# PDN.net
KiCad netlist of a schematic drawn in Altium Designer
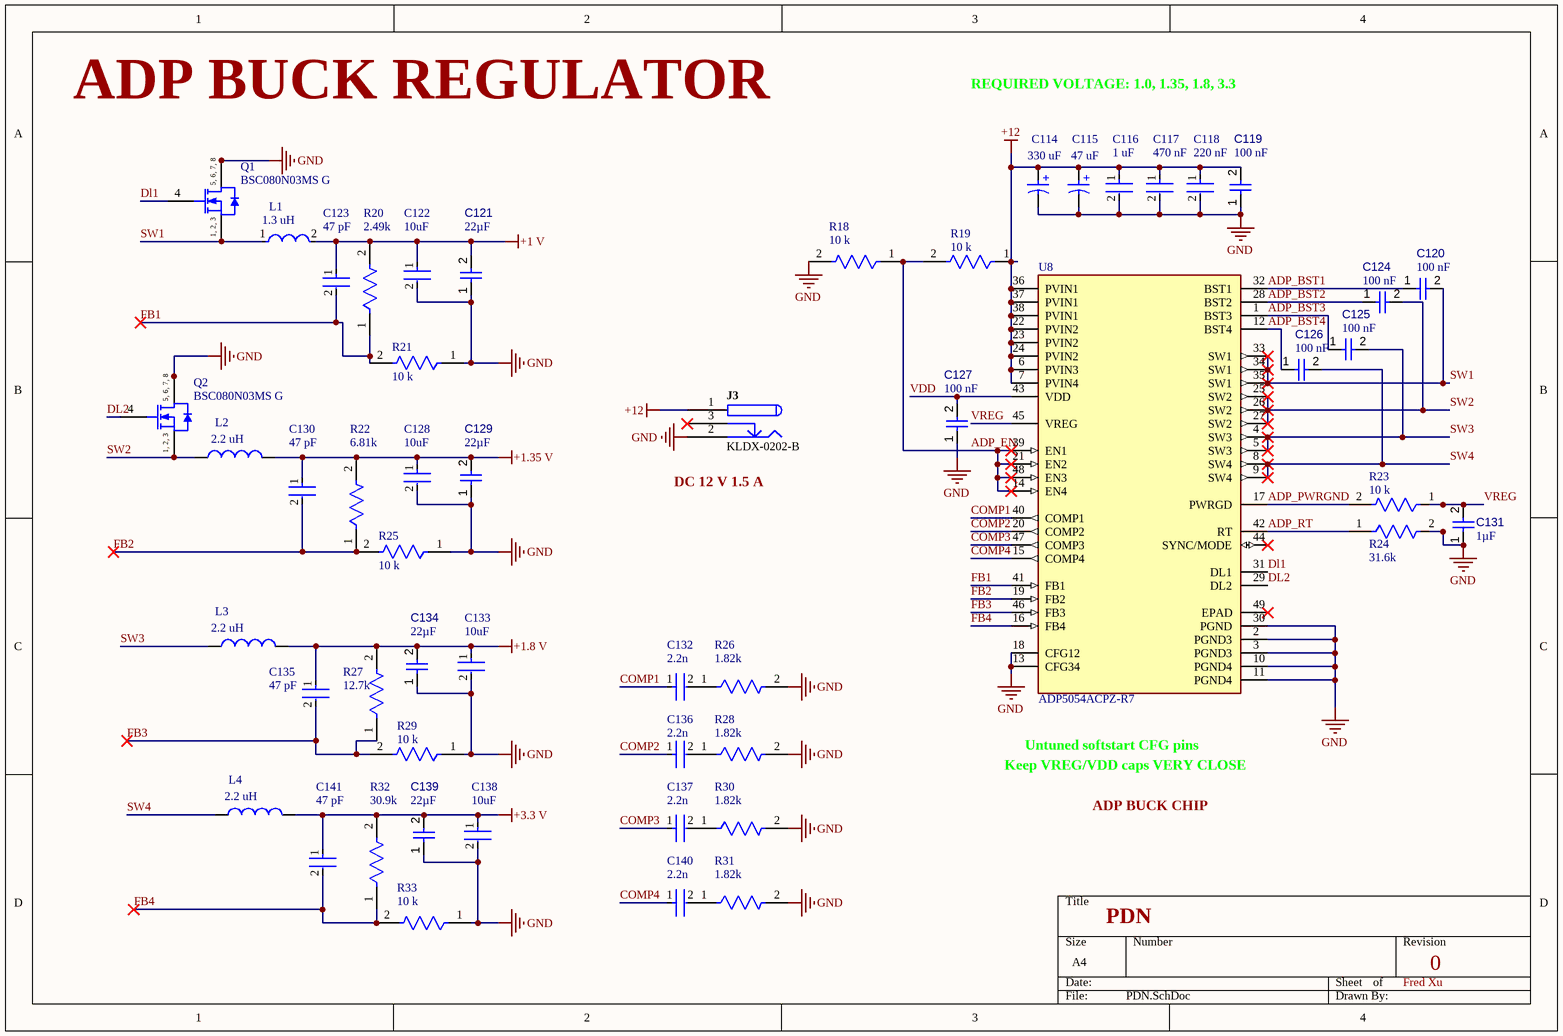
[diagram p0: PDN.SchDoc]

(export (version "E")
  (design (tool "Eeschema 10.0.6"))
  (components
    (comp (ref "C114")
      (value "330 uF")
      (footprint "WCAP-ATLI_D8H11.5")
      (fields (field (name "TOLERANCE") "20%"))
      (libsource (lib "Altium Content Vault") (part "Capacitor_Polarized"))
    )
    (comp (ref "C115")
      (value "47 uF")
      (footprint "WCAP-AT1H_D16H25")
      (description "Cap, 47Uf, 400V, Alu Elec, Radial Rohs Compliant: Yes")
      (libsource (lib "Altium Content Vault") (part "Capacitor_Polarized"))
    )
    (comp (ref "C116")
      (value "1 uF")
      (footprint "FP-GCM155-0_2-MFG")
      (description "Ceramic Capacitor for Automotive 1uF ±20% 10VDC X7S 0402 Paper T/R")
      (libsource (lib "Altium Content Vault") (part "11868f565c42a9108669ba33697ecf6"))
    )
    (comp (ref "C117")
      (value "470 nF")
      (footprint "FP-GRM155-0_05-IPC_B")
      (description "Chip Multilayer Ceramic Capacitors for General Purpose, 0402, 0.47uF, X7R, 15%, 20%, 10V")
      (fields (field (name "TOLERANCE") "20%"))
      (libsource (lib "Altium Content Vault") (part "02cd4be3c70576c341d710602a673aa"))
    )
    (comp (ref "C118")
      (value "220 nF")
      (footprint "FP-CGA2B-IPC_B")
      (description "Cap Ceramic 220nF 25V X7R 20% Pad SMD 0402 +125°C Automotive T/R")
      (fields (field (name "TOLERANCE") "20%"))
      (libsource (lib "Altium Content Vault") (part "b4654b650e69147ec39a6b967a45e02"))
    )
    (comp (ref "C119")
      (value "100 nF")
      (footprint "CAPC1005X56X25LL10T15")
      (description "Chip Capacitor, 0.1 uF, +/- 5%, 16 V, 0402 (1005 Metric)")
      (fields (field (name "TOLERANCE") "5%") (field (name "Comment") "0.1 uF"))
      (libsource (lib "Fred Xu") (part "CAP-NP-2"))
    )
    (comp (ref "C120")
      (value "100 nF")
      (footprint "CAPC1005X56X25LL10T15")
      (description "Chip Capacitor, 0.1 uF, +/- 5%, 16 V, 0402 (1005 Metric), 0.1-1 ohm ESR, 15 MHz-1nH ESL")
      (fields (field (name "TOLERANCE") "5%") (field (name "Comment") "0.1 uF"))
      (libsource (lib "Fred Xu") (part "CAP-NP-2"))
    )
    (comp (ref "C121")
      (value "22µF")
      (footprint "CAPC0805(2012)145_L")
      (description "Chip Capacitor, 22µF +/-40%, 16V, 0805, Thickness 1.45 mm, 5-50 mOhm,  0.5-2 nH")
      (fields (field (name "TOLERANCE") "5%") (field (name "Comment") "Capacitor 22µF +/-40% 16V 0805"))
      (libsource (lib "Fred Xu") (part "CAP-NP-2"))
    )
    (comp (ref "C122")
      (value "10uF")
      (footprint "FP-CL21-IPC_A")
      (fields (field (name "TOLERANCE") "10%"))
      (libsource (lib "Altium Content Vault") (part "b4654b650e69147ec39a6b967a45e02"))
    )
    (comp (ref "C123")
      (value "47 pF")
      (footprint "FP-GQM155-0_05-IPC_A")
      (description "Ceramic Capacitor 47pF  ±5% 100VDC C0G 0402 Paper T/R")
      (fields (field (name "TOLERANCE") "5%"))
      (libsource (lib "Altium Content Vault") (part "11868f565c42a9108669ba33697ecf6"))
    )
    (comp (ref "C124")
      (value "100 nF")
      (footprint "CAPC1005X56X25LL10T15")
      (description "Chip Capacitor, 0.1 uF, +/- 5%, 16 V, 0402 (1005 Metric), 0.1-1 ohm ESR, 15 MHz-1nH ESL")
      (fields (field (name "TOLERANCE") "5%") (field (name "Comment") "0.1 uF"))
      (libsource (lib "Fred Xu") (part "CAP-NP-2"))
    )
    (comp (ref "C125")
      (value "100 nF")
      (footprint "CAPC1005X56X25LL10T15")
      (description "Chip Capacitor, 0.1 uF, +/- 5%, 16 V, 0402 (1005 Metric), 0.1-1 ohm ESR, 15 MHz-1nH ESL")
      (fields (field (name "TOLERANCE") "5%") (field (name "Comment") "0.1 uF"))
      (libsource (lib "Fred Xu") (part "CAP-NP-2"))
    )
    (comp (ref "C126")
      (value "100 nF")
      (footprint "CAPC1005X56X25LL10T15")
      (description "Chip Capacitor, 0.1 uF, +/- 5%, 16 V, 0402 (1005 Metric), 0.1-1 ohm ESR, 15 MHz-1nH ESL")
      (fields (field (name "TOLERANCE") "5%") (field (name "Comment") "0.1 uF"))
      (libsource (lib "Fred Xu") (part "CAP-NP-2"))
    )
    (comp (ref "C127")
      (value "100 nF")
      (footprint "CAPC1005X56X25LL10T15")
      (description "Chip Capacitor, 0.1 uF, +/- 5%, 16 V, 0402 (1005 Metric)")
      (fields (field (name "TOLERANCE") "5%") (field (name "Comment") "0.1 uF"))
      (libsource (lib "Fred Xu") (part "CAP-NP-2"))
    )
    (comp (ref "C128")
      (value "10uF")
      (footprint "FP-CL21-IPC_A")
      (fields (field (name "TOLERANCE") "10%"))
      (libsource (lib "Altium Content Vault") (part "b4654b650e69147ec39a6b967a45e02"))
    )
    (comp (ref "C129")
      (value "22µF")
      (footprint "CAPC0805(2012)145_L")
      (description "Chip Capacitor, 22µF +/-40%, 16V, 0805, Thickness 1.45 mm, 5-50 mOhm,  0.5-2 nH")
      (fields (field (name "TOLERANCE") "5%") (field (name "Comment") "Capacitor 22µF +/-40% 16V 0805"))
      (libsource (lib "Fred Xu") (part "CAP-NP-2"))
    )
    (comp (ref "C130")
      (value "47 pF")
      (footprint "FP-GQM155-0_05-IPC_A")
      (description "Ceramic Capacitor 47pF  ±5% 100VDC C0G 0402 Paper T/R")
      (fields (field (name "TOLERANCE") "5%"))
      (libsource (lib "Altium Content Vault") (part "11868f565c42a9108669ba33697ecf6"))
    )
    (comp (ref "C131")
      (value "1µF")
      (footprint "CAPC0603(1608)100_L")
      (description "Chip Capacitor, 1µF +/-40%, 50V, 0603, Thickness 1 mm")
      (fields (field (name "TOLERANCE") "10%") (field (name "Comment") "Capacitor 1µF +/-40% 50V 0603"))
      (libsource (lib "Fred Xu") (part "CAP-NP-2"))
    )
    (comp (ref "C132")
      (value "2.2n")
      (footprint "FP-C0402-BB-MFG")
      (description "C0402 2,200 pF C0G 0.02 25 V")
      (fields
        (field (name "MANUFACTURER PART NUMBER") "C0402C222G3GACTU")
        (field (name "OCTOPART") "https://octopart.com/c0402c222g3gactu-kemet-87368565")
      )
      (libsource (lib "Altium Content Vault") (part "b4654b650e69147ec39a6b967a45e02"))
    )
    (comp (ref "C133")
      (value "10uF")
      (footprint "FP-CL21-IPC_A")
      (fields (field (name "TOLERANCE") "10%"))
      (libsource (lib "Altium Content Vault") (part "b4654b650e69147ec39a6b967a45e02"))
    )
    (comp (ref "C134")
      (value "22µF")
      (footprint "CAPC0805(2012)145_L")
      (description "Chip Capacitor, 22µF +/-40%, 16V, 0805, Thickness 1.45 mm, 5-50 mOhm,  0.5-2 nH")
      (fields (field (name "TOLERANCE") "5%") (field (name "Comment") "Capacitor 22µF +/-40% 16V 0805"))
      (libsource (lib "Fred Xu") (part "CAP-NP-2"))
    )
    (comp (ref "C135")
      (value "47 pF")
      (footprint "FP-GQM155-0_05-IPC_A")
      (description "Ceramic Capacitor 47pF  ±5% 100VDC C0G 0402 Paper T/R")
      (fields (field (name "TOLERANCE") "5%"))
      (libsource (lib "Altium Content Vault") (part "11868f565c42a9108669ba33697ecf6"))
    )
    (comp (ref "C136")
      (value "2.2n")
      (footprint "FP-C0402-BB-MFG")
      (description "C0402 2,200 pF C0G 0.02 25 V")
      (fields
        (field (name "MANUFACTURER PART NUMBER") "C0402C222G3GACTU")
        (field (name "OCTOPART") "https://octopart.com/c0402c222g3gactu-kemet-87368565")
      )
      (libsource (lib "Altium Content Vault") (part "b4654b650e69147ec39a6b967a45e02"))
    )
    (comp (ref "C137")
      (value "2.2n")
      (footprint "FP-C0402-BB-MFG")
      (description "C0402 2,200 pF C0G 0.02 25 V")
      (fields
        (field (name "MANUFACTURER PART NUMBER") "C0402C222G3GACTU")
        (field (name "OCTOPART") "https://octopart.com/c0402c222g3gactu-kemet-87368565")
      )
      (libsource (lib "Altium Content Vault") (part "b4654b650e69147ec39a6b967a45e02"))
    )
    (comp (ref "C138")
      (value "10uF")
      (footprint "FP-CL21-IPC_A")
      (fields (field (name "TOLERANCE") "10%"))
      (libsource (lib "Altium Content Vault") (part "b4654b650e69147ec39a6b967a45e02"))
    )
    (comp (ref "C139")
      (value "22µF")
      (footprint "CAPC0805(2012)145_L")
      (description "Chip Capacitor, 22µF +/-40%, 16V, 0805, Thickness 1.45 mm, 5-50 mOhm,  0.5-2 nH")
      (fields (field (name "TOLERANCE") "5%") (field (name "Comment") "Capacitor 22µF +/-40% 16V 0805"))
      (libsource (lib "Fred Xu") (part "CAP-NP-2"))
    )
    (comp (ref "C140")
      (value "2.2n")
      (footprint "FP-C0402-BB-MFG")
      (description "C0402 2,200 pF C0G 0.02 25 V")
      (fields
        (field (name "MANUFACTURER PART NUMBER") "C0402C222G3GACTU")
        (field (name "OCTOPART") "https://octopart.com/c0402c222g3gactu-kemet-87368565")
      )
      (libsource (lib "Altium Content Vault") (part "b4654b650e69147ec39a6b967a45e02"))
    )
    (comp (ref "C141")
      (value "47 pF")
      (footprint "FP-GQM155-0_05-IPC_A")
      (description "Ceramic Capacitor 47pF  ±5% 100VDC C0G 0402 Paper T/R")
      (fields (field (name "TOLERANCE") "5%"))
      (libsource (lib "Altium Content Vault") (part "11868f565c42a9108669ba33697ecf6"))
    )
    (comp (ref "J3")
      (value "KLDX-0202-B")
      (footprint "KYCN-KLDX-0202-B_V")
      (description "3 Conductor Power Jack, 2 break 2 aux contacts")
      (libsource (lib "Altium Content Vault") (part "KYCN-KLDX-0202-B-3"))
    )
    (comp (ref "L1")
      (value "1.3 uH")
      (footprint "FP-NR6045-MFG")
      (description "Shielded Wirewound Inductor 1.3uH 30% 4A 20.8mΩ SMD")
      (fields (field (name "TOLERANCE") "30%"))
      (libsource (lib "Altium Content Vault") (part "725321dda6339637d4d059423bc1c3c"))
    )
    (comp (ref "L2")
      (value "2.2 uH")
      (footprint "WE-PMFI_322512")
      (description "Power Ind, 2.2UH, 4.1A, Shielded, 1210 Rohs Compliant: Yes")
      (libsource (lib "Altium Content Vault") (part "Inductor - 1"))
    )
    (comp (ref "L3")
      (value "2.2 uH")
      (footprint "WE-PMFI_322512")
      (description "Power Ind, 2.2UH, 4.1A, Shielded, 1210 Rohs Compliant: Yes")
      (libsource (lib "Altium Content Vault") (part "Inductor - 1"))
    )
    (comp (ref "L4")
      (value "2.2 uH")
      (footprint "WE-PMFI_322512")
      (description "Power Ind, 2.2UH, 4.1A, Shielded, 1210 Rohs Compliant: Yes")
      (libsource (lib "Altium Content Vault") (part "Inductor - 1"))
    )
    (comp (ref "Q1")
      (value "BSC080N03MS G")
      (footprint "INF-PG-TDSON-8-1_V")
      (fields (field (name "MANUFACTURER") "Infineon"))
      (libsource (lib "Altium Content Vault") (part "INF-NEMOS-SSSGDDDD-8"))
    )
    (comp (ref "Q2")
      (value "BSC080N03MS G")
      (footprint "INF-PG-TDSON-8-1_V")
      (fields (field (name "MANUFACTURER") "Infineon"))
      (libsource (lib "Altium Content Vault") (part "INF-NEMOS-SSSGDDDD-8"))
    )
    (comp (ref "R18")
      (value "10 k")
      (footprint "FP-AC0603-IPC_A")
      (description "RES 10kΩ 5.00% 0.2W 0603")
      (libsource (lib "Altium Content Vault") (part "1029c3af85768c4190bb7ad29bc67b5"))
    )
    (comp (ref "R19")
      (value "10 k")
      (footprint "FP-AC0603-IPC_A")
      (description "RES 10kΩ 5.00% 0.2W 0603")
      (libsource (lib "Altium Content Vault") (part "1029c3af85768c4190bb7ad29bc67b5"))
    )
    (comp (ref "R20")
      (value "2.49k")
      (footprint "FP-RT0603-MFG")
      (description "RES SMD 2.49K OHM 0.1% 1/10W")
      (fields
        (field (name "OCTOPART") "https://octopart.com/rt0603bre072k49l-yageo-1264492")
        (field (name "TOLERANCE") "0.001")
      )
      (libsource (lib "Altium Content Vault") (part "1029c3af85768c4190bb7ad29bc67b5"))
    )
    (comp (ref "R21")
      (value "10 k")
      (footprint "FP-AC0603-IPC_A")
      (description "RES 10kΩ 5.00% 0.2W 0603")
      (libsource (lib "Altium Content Vault") (part "1029c3af85768c4190bb7ad29bc67b5"))
    )
    (comp (ref "R22")
      (value "6.81k")
      (footprint "FP-RNCP0603-IPC_A")
      (description "6.81kΩ ±1% 0.125W 0603 High Power Anti-Sulfur Thin Film Chip Resistor")
      (fields (field (name "TOLERANCE") "1%"))
      (libsource (lib "Altium Content Vault") (part "1029c3af85768c4190bb7ad29bc67b5"))
    )
    (comp (ref "R23")
      (value "10 k")
      (footprint "FP-AC0603-IPC_A")
      (description "RES 10kΩ 5.00% 0.2W 0603")
      (libsource (lib "Altium Content Vault") (part "1029c3af85768c4190bb7ad29bc67b5"))
    )
    (comp (ref "R24")
      (value "31.6k")
      (footprint "FP-RMCF0402-IPC_A")
      (description "31.6kΩ ±1% 0.063W 0402 Thick Film Chip Resistor AEC-Q200 compliant")
      (fields (field (name "TOLERANCE") "1%"))
      (libsource (lib "Altium Content Vault") (part "1029c3af85768c4190bb7ad29bc67b5"))
    )
    (comp (ref "R25")
      (value "10 k")
      (footprint "FP-AC0603-IPC_A")
      (description "RES 10kΩ 5.00% 0.2W 0603")
      (libsource (lib "Altium Content Vault") (part "1029c3af85768c4190bb7ad29bc67b5"))
    )
    (comp (ref "R26")
      (value "1.82k")
      (footprint "FP-CRCW0402-e3-IPC_A")
      (description "RES Thick Film, 1.82kΩ, 1%, 0.063W, 100ppm/°C, 0402")
      (fields (field (name "TOLERANCE") "5%"))
      (libsource (lib "Altium Content Vault") (part "1029c3af85768c4190bb7ad29bc67b5"))
    )
    (comp (ref "R27")
      (value "12.7k")
      (footprint "FP-RP73P-1E-MFG")
      (description "RP73P 0402 12.7KΩ 0.1W 25ppm/°C 0.10% 50V")
      (fields
        (field (name "MANUFACTURER PART NUMBER") "RP73PF1E12K7BTD")
        (field (name "OCTOPART") "https://octopart.com/rp73pf1e12k7btd-te+connectivity-89229930")
      )
      (libsource (lib "Altium Content Vault") (part "1029c3af85768c4190bb7ad29bc67b5"))
    )
    (comp (ref "R28")
      (value "1.82k")
      (footprint "FP-CRCW0402-e3-IPC_A")
      (description "RES Thick Film, 1.82kΩ, 1%, 0.063W, 100ppm/°C, 0402")
      (fields (field (name "TOLERANCE") "5%"))
      (libsource (lib "Altium Content Vault") (part "1029c3af85768c4190bb7ad29bc67b5"))
    )
    (comp (ref "R29")
      (value "10 k")
      (footprint "FP-AC0603-IPC_A")
      (description "RES 10kΩ 5.00% 0.2W 0603")
      (libsource (lib "Altium Content Vault") (part "1029c3af85768c4190bb7ad29bc67b5"))
    )
    (comp (ref "R30")
      (value "1.82k")
      (footprint "FP-CRCW0402-e3-IPC_A")
      (description "RES Thick Film, 1.82kΩ, 1%, 0.063W, 100ppm/°C, 0402")
      (fields (field (name "TOLERANCE") "5%"))
      (libsource (lib "Altium Content Vault") (part "1029c3af85768c4190bb7ad29bc67b5"))
    )
    (comp (ref "R31")
      (value "1.82k")
      (footprint "FP-CRCW0402-e3-IPC_A")
      (description "RES Thick Film, 1.82kΩ, 1%, 0.063W, 100ppm/°C, 0402")
      (fields (field (name "TOLERANCE") "5%"))
      (libsource (lib "Altium Content Vault") (part "1029c3af85768c4190bb7ad29bc67b5"))
    )
    (comp (ref "R32")
      (value "30.9k")
      (footprint "FP-RK73H1E-IPC_C")
      (description "30.9kΩ ±1% 0.1W Chip Resistor 0402 Thick Film AEC-Q200 Qualified")
      (fields (field (name "TOLERANCE") "1%"))
      (libsource (lib "Altium Content Vault") (part "1029c3af85768c4190bb7ad29bc67b5"))
    )
    (comp (ref "R33")
      (value "10 k")
      (footprint "FP-AC0603-IPC_A")
      (description "RES 10kΩ 5.00% 0.2W 0603")
      (libsource (lib "Altium Content Vault") (part "1029c3af85768c4190bb7ad29bc67b5"))
    )
    (comp (ref "U8")
      (value "ADP5054ACPZ-R7")
      (footprint "FP-CP-48-16-IPC_C")
      (description "IC REG CTRLR BUCK 48LFCSP")
      (libsource (lib "Altium Content Vault") (part "31682ca594b7aca0750dbff9fdd2121"))
    )
  )
  (nets
    (net (code "1") (name "+1 V") (class "Default")
      (node (ref "C121") (pin "2") (pinfunction "2_2") (pintype "passive"))
      (node (ref "C122") (pin "1") (pinfunction "1_1") (pintype "passive"))
      (node (ref "C123") (pin "1") (pinfunction "1_1") (pintype "passive"))
      (node (ref "L1") (pin "2") (pinfunction "2_2") (pintype "passive"))
      (node (ref "R20") (pin "2") (pinfunction "2_2") (pintype "passive"))
    )
    (net (code "2") (name "+1.8 V") (class "Default")
      (node (ref "C133") (pin "1") (pinfunction "1_1") (pintype "passive"))
      (node (ref "C134") (pin "2") (pinfunction "2_2") (pintype "passive"))
      (node (ref "C135") (pin "1") (pinfunction "1_1") (pintype "passive"))
      (node (ref "L3") (pin "2") (pinfunction "2_2") (pintype "passive"))
      (node (ref "R27") (pin "2") (pinfunction "2_2") (pintype "passive"))
    )
    (net (code "3") (name "+1.35 V") (class "Default")
      (node (ref "C128") (pin "1") (pinfunction "1_1") (pintype "passive"))
      (node (ref "C129") (pin "2") (pinfunction "2_2") (pintype "passive"))
      (node (ref "C130") (pin "1") (pinfunction "1_1") (pintype "passive"))
      (node (ref "L2") (pin "2") (pinfunction "2_2") (pintype "passive"))
      (node (ref "R22") (pin "2") (pinfunction "2_2") (pintype "passive"))
    )
    (net (code "4") (name "+3.3 V") (class "Default")
      (node (ref "C138") (pin "1") (pinfunction "1_1") (pintype "passive"))
      (node (ref "C139") (pin "2") (pinfunction "2_2") (pintype "passive"))
      (node (ref "C141") (pin "1") (pinfunction "1_1") (pintype "passive"))
      (node (ref "L4") (pin "2") (pinfunction "2_2") (pintype "passive"))
      (node (ref "R32") (pin "2") (pinfunction "2_2") (pintype "passive"))
    )
    (net (code "5") (name "+12") (class "Default")
      (node (ref "C114") (pin "1") (pinfunction "P_1") (pintype "passive"))
      (node (ref "C115") (pin "1") (pinfunction "P_1") (pintype "passive"))
      (node (ref "C116") (pin "1") (pinfunction "1_1") (pintype "passive"))
      (node (ref "C117") (pin "1") (pinfunction "1_1") (pintype "passive"))
      (node (ref "C118") (pin "1") (pinfunction "1_1") (pintype "passive"))
      (node (ref "C119") (pin "2") (pinfunction "2_2") (pintype "passive"))
      (node (ref "J3") (pin "1") (pintype "power_in"))
      (node (ref "R19") (pin "1") (pinfunction "1_1") (pintype "passive"))
      (node (ref "U8") (pin "22") (pinfunction "PVIN2_22") (pintype "power_in"))
      (node (ref "U8") (pin "23") (pinfunction "PVIN2_23") (pintype "power_in"))
      (node (ref "U8") (pin "24") (pinfunction "PVIN2_24") (pintype "power_in"))
      (node (ref "U8") (pin "36") (pinfunction "PVIN1_36") (pintype "power_in"))
      (node (ref "U8") (pin "37") (pinfunction "PVIN1_37") (pintype "power_in"))
      (node (ref "U8") (pin "38") (pinfunction "PVIN1_38") (pintype "power_in"))
      (node (ref "U8") (pin "6") (pinfunction "PVIN3_6") (pintype "power_in"))
      (node (ref "U8") (pin "7") (pinfunction "PVIN4_7") (pintype "power_in"))
    )
    (net (code "6") (name "/ADP_BST1") (class "Default")
      (node (ref "C120") (pin "1") (pinfunction "1_1") (pintype "passive"))
      (node (ref "U8") (pin "32") (pinfunction "BST1_32") (pintype "power_in"))
    )
    (net (code "7") (name "/ADP_BST2") (class "Default")
      (node (ref "C124") (pin "1") (pinfunction "1_1") (pintype "passive"))
      (node (ref "U8") (pin "28") (pinfunction "BST2_28") (pintype "power_in"))
    )
    (net (code "8") (name "/ADP_BST3") (class "Default")
      (node (ref "C125") (pin "1") (pinfunction "1_1") (pintype "passive"))
      (node (ref "U8") (pin "1") (pinfunction "BST3_1") (pintype "power_in"))
    )
    (net (code "9") (name "/ADP_BST4") (class "Default")
      (node (ref "C126") (pin "1") (pinfunction "1_1") (pintype "passive"))
      (node (ref "U8") (pin "12") (pinfunction "BST4_12") (pintype "power_in"))
    )
    (net (code "10") (name "/ADP_EN") (class "Default")
      (node (ref "R18") (pin "1") (pinfunction "1_1") (pintype "passive"))
      (node (ref "R19") (pin "2") (pinfunction "2_2") (pintype "passive"))
      (node (ref "U8") (pin "14") (pinfunction "EN4_14") (pintype "input"))
      (node (ref "U8") (pin "21") (pinfunction "EN2_21") (pintype "input"))
      (node (ref "U8") (pin "39") (pinfunction "EN1_39") (pintype "input"))
      (node (ref "U8") (pin "48") (pinfunction "EN3_48") (pintype "input"))
    )
    (net (code "11") (name "/ADP_PWRGND") (class "Default")
      (node (ref "R23") (pin "2") (pinfunction "2_2") (pintype "passive"))
      (node (ref "U8") (pin "17") (pinfunction "PWRGD_17") (pintype "open_collector"))
    )
    (net (code "12") (name "/ADP_RT") (class "Default")
      (node (ref "R24") (pin "1") (pinfunction "1_1") (pintype "passive"))
      (node (ref "U8") (pin "42") (pinfunction "RT_42") (pintype "passive"))
    )
    (net (code "13") (name "/COMP1") (class "Default")
      (node (ref "C132") (pin "1") (pinfunction "1_1") (pintype "passive"))
      (node (ref "U8") (pin "40") (pinfunction "COMP1_40") (pintype "output"))
    )
    (net (code "14") (name "/COMP2") (class "Default")
      (node (ref "C136") (pin "1") (pinfunction "1_1") (pintype "passive"))
      (node (ref "U8") (pin "20") (pinfunction "COMP2_20") (pintype "output"))
    )
    (net (code "15") (name "/COMP3") (class "Default")
      (node (ref "C137") (pin "1") (pinfunction "1_1") (pintype "passive"))
      (node (ref "U8") (pin "47") (pinfunction "COMP3_47") (pintype "output"))
    )
    (net (code "16") (name "/COMP4") (class "Default")
      (node (ref "C140") (pin "1") (pinfunction "1_1") (pintype "passive"))
      (node (ref "U8") (pin "15") (pinfunction "COMP4_15") (pintype "output"))
    )
    (net (code "17") (name "/DL2") (class "Default")
      (node (ref "Q2") (pin "4") (pinfunction "GATE_4") (pintype "passive"))
      (node (ref "U8") (pin "29") (pinfunction "DL2_29") (pintype "passive"))
    )
    (net (code "18") (name "/Dl1") (class "Default")
      (node (ref "Q1") (pin "4") (pinfunction "GATE_4") (pintype "passive"))
      (node (ref "U8") (pin "31") (pinfunction "DL1_31") (pintype "passive"))
    )
    (net (code "19") (name "/FB1") (class "Default")
      (node (ref "C123") (pin "2") (pinfunction "2_2") (pintype "passive"))
      (node (ref "R20") (pin "1") (pinfunction "1_1") (pintype "passive"))
      (node (ref "R21") (pin "2") (pinfunction "2_2") (pintype "passive"))
      (node (ref "U8") (pin "41") (pinfunction "FB1_41") (pintype "input"))
    )
    (net (code "20") (name "/FB2") (class "Default")
      (node (ref "C130") (pin "2") (pinfunction "2_2") (pintype "passive"))
      (node (ref "R22") (pin "1") (pinfunction "1_1") (pintype "passive"))
      (node (ref "R25") (pin "2") (pinfunction "2_2") (pintype "passive"))
      (node (ref "U8") (pin "19") (pinfunction "FB2_19") (pintype "input"))
    )
    (net (code "21") (name "/FB3") (class "Default")
      (node (ref "C135") (pin "2") (pinfunction "2_2") (pintype "passive"))
      (node (ref "R27") (pin "1") (pinfunction "1_1") (pintype "passive"))
      (node (ref "R29") (pin "2") (pinfunction "2_2") (pintype "passive"))
      (node (ref "U8") (pin "46") (pinfunction "FB3_46") (pintype "input"))
    )
    (net (code "22") (name "/FB4") (class "Default")
      (node (ref "C141") (pin "2") (pinfunction "2_2") (pintype "passive"))
      (node (ref "R32") (pin "1") (pinfunction "1_1") (pintype "passive"))
      (node (ref "R33") (pin "2") (pinfunction "2_2") (pintype "passive"))
      (node (ref "U8") (pin "16") (pinfunction "FB4_16") (pintype "input"))
    )
    (net (code "23") (name "/SW1") (class "Default")
      (node (ref "C120") (pin "2") (pinfunction "2_2") (pintype "passive"))
      (node (ref "L1") (pin "1") (pinfunction "1_1") (pintype "passive"))
      (node (ref "Q1") (pin "1") (pinfunction "SOURCE_1") (pintype "passive"))
      (node (ref "Q1") (pin "2") (pinfunction "SOURCE_2") (pintype "passive"))
      (node (ref "Q1") (pin "3") (pinfunction "SOURCE_3") (pintype "passive"))
      (node (ref "U8") (pin "33") (pinfunction "SW1_33") (pintype "output"))
      (node (ref "U8") (pin "34") (pinfunction "SW1_34") (pintype "output"))
      (node (ref "U8") (pin "35") (pinfunction "SW1_35") (pintype "output"))
    )
    (net (code "24") (name "/SW2") (class "Default")
      (node (ref "C124") (pin "2") (pinfunction "2_2") (pintype "passive"))
      (node (ref "L2") (pin "1") (pinfunction "1_1") (pintype "passive"))
      (node (ref "Q2") (pin "1") (pinfunction "SOURCE_1") (pintype "passive"))
      (node (ref "Q2") (pin "2") (pinfunction "SOURCE_2") (pintype "passive"))
      (node (ref "Q2") (pin "3") (pinfunction "SOURCE_3") (pintype "passive"))
      (node (ref "U8") (pin "25") (pinfunction "SW2_25") (pintype "output"))
      (node (ref "U8") (pin "26") (pinfunction "SW2_26") (pintype "output"))
      (node (ref "U8") (pin "27") (pinfunction "SW2_27") (pintype "output"))
    )
    (net (code "25") (name "/SW3") (class "Default")
      (node (ref "C125") (pin "2") (pinfunction "2_2") (pintype "passive"))
      (node (ref "L3") (pin "1") (pinfunction "1_1") (pintype "passive"))
      (node (ref "U8") (pin "4") (pinfunction "SW3_4") (pintype "output"))
      (node (ref "U8") (pin "5") (pinfunction "SW3_5") (pintype "output"))
    )
    (net (code "26") (name "/SW4") (class "Default")
      (node (ref "C126") (pin "2") (pinfunction "2_2") (pintype "passive"))
      (node (ref "L4") (pin "1") (pinfunction "1_1") (pintype "passive"))
      (node (ref "U8") (pin "8") (pinfunction "SW4_8") (pintype "output"))
      (node (ref "U8") (pin "9") (pinfunction "SW4_9") (pintype "output"))
    )
    (net (code "27") (name "/VDD") (class "Default")
      (node (ref "C127") (pin "2") (pinfunction "2_2") (pintype "passive"))
      (node (ref "U8") (pin "43") (pinfunction "VDD_43") (pintype "power_in"))
    )
    (net (code "28") (name "/VREG") (class "Default")
      (node (ref "C131") (pin "2") (pinfunction "2_2") (pintype "passive"))
      (node (ref "R23") (pin "1") (pinfunction "1_1") (pintype "passive"))
      (node (ref "U8") (pin "45") (pinfunction "VREG_45") (pintype "power_in"))
    )
    (net (code "29") (name "GND") (class "Default")
      (node (ref "C114") (pin "2") (pinfunction "N_2") (pintype "passive"))
      (node (ref "C115") (pin "2") (pinfunction "N_2") (pintype "passive"))
      (node (ref "C116") (pin "2") (pinfunction "2_2") (pintype "passive"))
      (node (ref "C117") (pin "2") (pinfunction "2_2") (pintype "passive"))
      (node (ref "C118") (pin "2") (pinfunction "2_2") (pintype "passive"))
      (node (ref "C119") (pin "1") (pinfunction "1_1") (pintype "passive"))
      (node (ref "C121") (pin "1") (pinfunction "1_1") (pintype "passive"))
      (node (ref "C122") (pin "2") (pinfunction "2_2") (pintype "passive"))
      (node (ref "C127") (pin "1") (pinfunction "1_1") (pintype "passive"))
      (node (ref "C128") (pin "2") (pinfunction "2_2") (pintype "passive"))
      (node (ref "C129") (pin "1") (pinfunction "1_1") (pintype "passive"))
      (node (ref "C131") (pin "1") (pinfunction "1_1") (pintype "passive"))
      (node (ref "C133") (pin "2") (pinfunction "2_2") (pintype "passive"))
      (node (ref "C134") (pin "1") (pinfunction "1_1") (pintype "passive"))
      (node (ref "C138") (pin "2") (pinfunction "2_2") (pintype "passive"))
      (node (ref "C139") (pin "1") (pinfunction "1_1") (pintype "passive"))
      (node (ref "J3") (pin "2") (pintype "power_in"))
      (node (ref "Q1") (pin "5") (pinfunction "DRAIN_5") (pintype "passive"))
      (node (ref "Q1") (pin "6") (pinfunction "DRAIN_6") (pintype "passive"))
      (node (ref "Q1") (pin "7") (pinfunction "DRAIN_7") (pintype "passive"))
      (node (ref "Q1") (pin "8") (pinfunction "DRAIN_8") (pintype "passive"))
      (node (ref "Q2") (pin "5") (pinfunction "DRAIN_5") (pintype "passive"))
      (node (ref "Q2") (pin "6") (pinfunction "DRAIN_6") (pintype "passive"))
      (node (ref "Q2") (pin "7") (pinfunction "DRAIN_7") (pintype "passive"))
      (node (ref "Q2") (pin "8") (pinfunction "DRAIN_8") (pintype "passive"))
      (node (ref "R18") (pin "2") (pinfunction "2_2") (pintype "passive"))
      (node (ref "R21") (pin "1") (pinfunction "1_1") (pintype "passive"))
      (node (ref "R24") (pin "2") (pinfunction "2_2") (pintype "passive"))
      (node (ref "R25") (pin "1") (pinfunction "1_1") (pintype "passive"))
      (node (ref "R26") (pin "2") (pinfunction "2_2") (pintype "passive"))
      (node (ref "R28") (pin "2") (pinfunction "2_2") (pintype "passive"))
      (node (ref "R29") (pin "1") (pinfunction "1_1") (pintype "passive"))
      (node (ref "R30") (pin "2") (pinfunction "2_2") (pintype "passive"))
      (node (ref "R31") (pin "2") (pinfunction "2_2") (pintype "passive"))
      (node (ref "R33") (pin "1") (pinfunction "1_1") (pintype "passive"))
      (node (ref "U8") (pin "10") (pinfunction "PGND4_10") (pintype "power_in"))
      (node (ref "U8") (pin "11") (pinfunction "PGND4_11") (pintype "power_in"))
      (node (ref "U8") (pin "13") (pinfunction "CFG34_13") (pintype "passive"))
      (node (ref "U8") (pin "18") (pinfunction "CFG12_18") (pintype "passive"))
      (node (ref "U8") (pin "2") (pinfunction "PGND3_2") (pintype "power_in"))
      (node (ref "U8") (pin "3") (pinfunction "PGND3_3") (pintype "power_in"))
      (node (ref "U8") (pin "30") (pinfunction "PGND_30") (pintype "power_in"))
    )
    (net (code "30") (name "Net-(C132-Pad2)") (class "Default")
      (node (ref "C132") (pin "2") (pinfunction "2_2") (pintype "passive"))
      (node (ref "R26") (pin "1") (pinfunction "1_1") (pintype "passive"))
    )
    (net (code "31") (name "Net-(C136-Pad2)") (class "Default")
      (node (ref "C136") (pin "2") (pinfunction "2_2") (pintype "passive"))
      (node (ref "R28") (pin "1") (pinfunction "1_1") (pintype "passive"))
    )
    (net (code "32") (name "Net-(C137-Pad2)") (class "Default")
      (node (ref "C137") (pin "2") (pinfunction "2_2") (pintype "passive"))
      (node (ref "R30") (pin "1") (pinfunction "1_1") (pintype "passive"))
    )
    (net (code "33") (name "Net-(C140-Pad2)") (class "Default")
      (node (ref "C140") (pin "2") (pinfunction "2_2") (pintype "passive"))
      (node (ref "R31") (pin "1") (pinfunction "1_1") (pintype "passive"))
    )
    (net (code "34") (name "unconnected-(J3-Pad3)") (class "Default")
      (node (ref "J3") (pin "3") (pintype "power_in+no_connect"))
    )
    (net (code "35") (name "unconnected-(U8-EPAD-Pad49)") (class "Default")
      (node (ref "U8") (pin "49") (pinfunction "EPAD_49") (pintype "power_in+no_connect"))
    )
    (net (code "36") (name "unconnected-(U8-SYNC{slash}MODE-Pad44)") (class "Default")
      (node (ref "U8") (pin "44") (pinfunction "SYNC/MODE_44") (pintype "bidirectional+no_connect"))
    )
  )
)
